# PowerSupplySimple.net
KiCad netlist of a schematic drawn in EAGLE
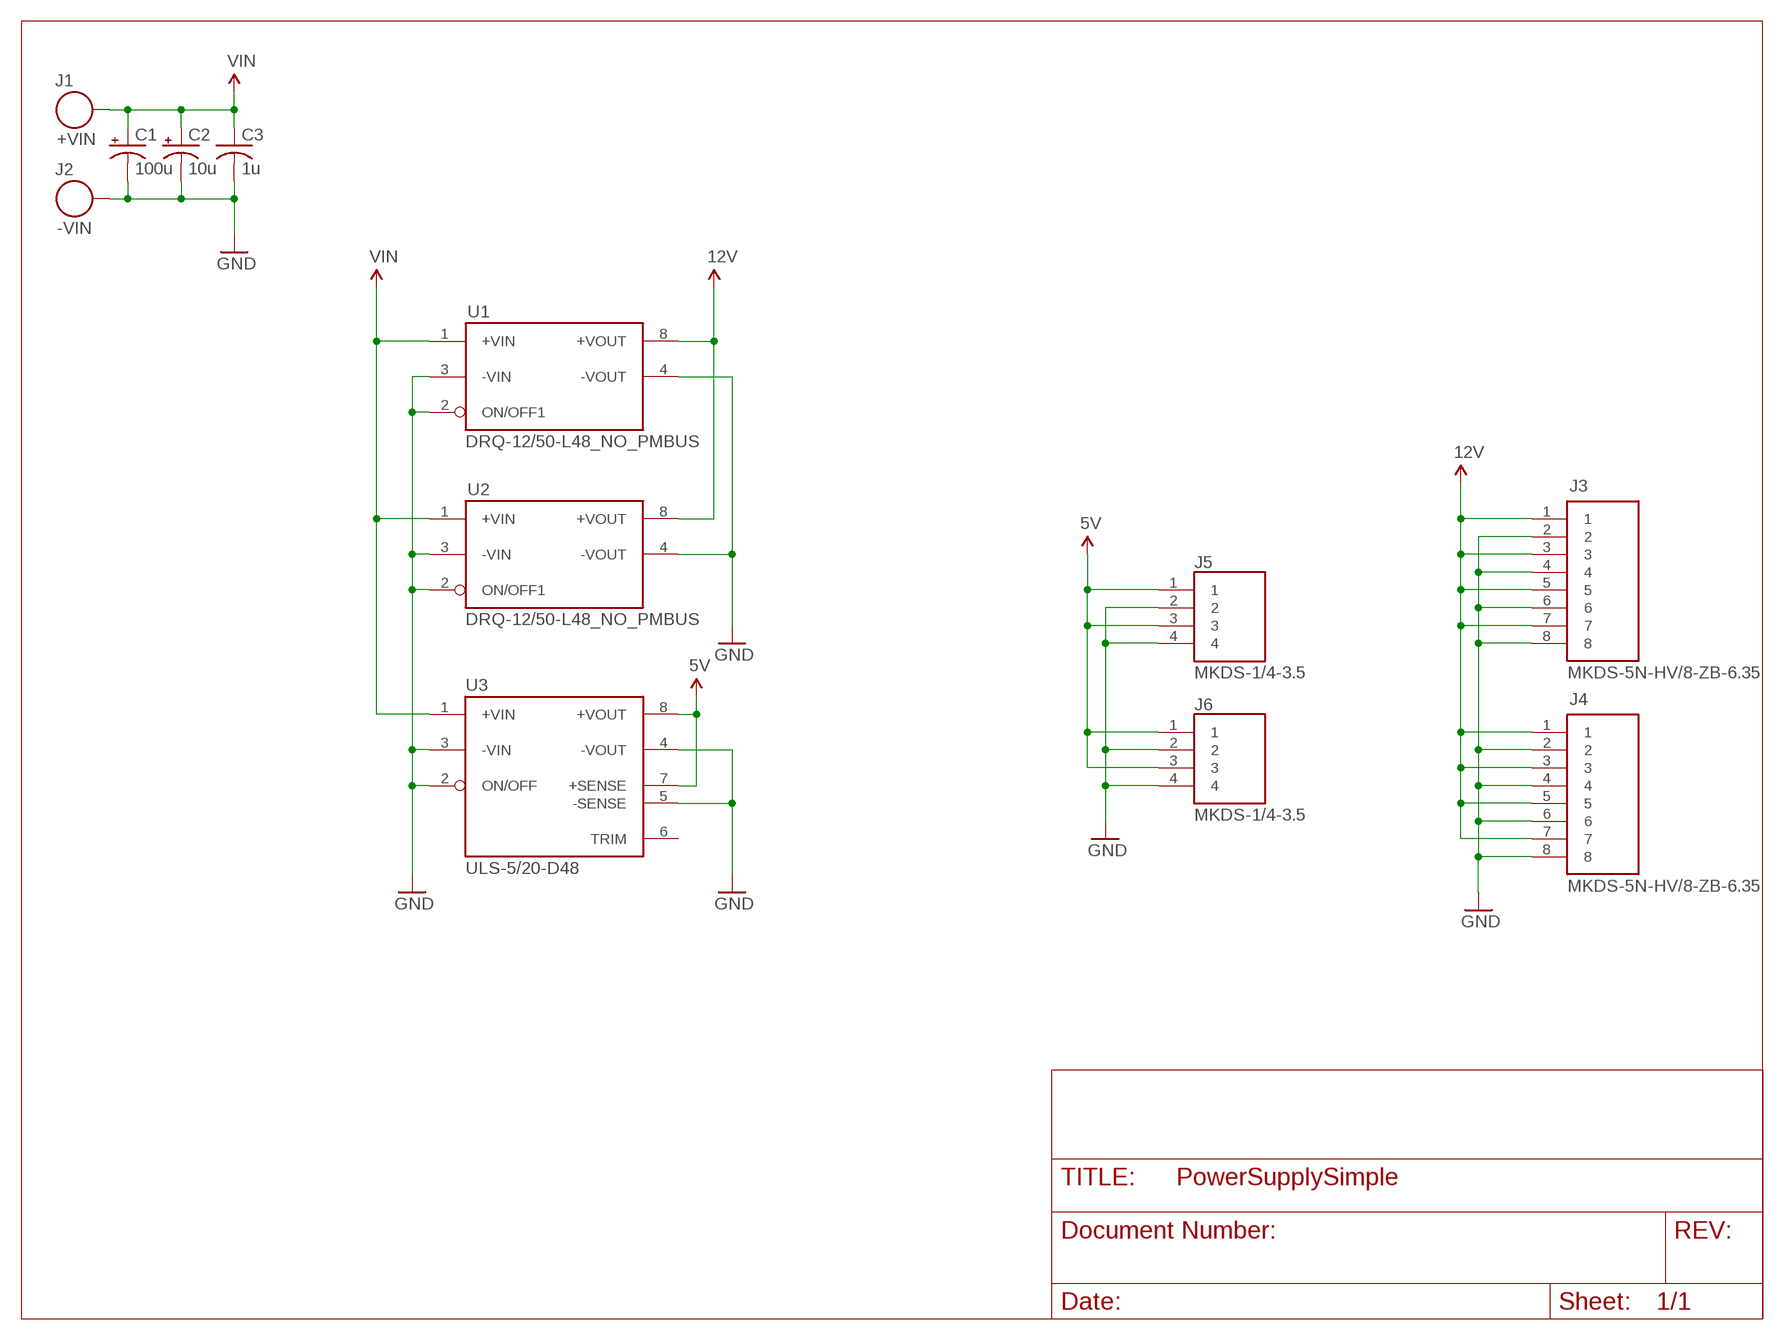
[diagram p0: schematic, sheet 1]

(export (version "E")
  (design (tool "Eeschema 10.0.6"))
  (components
    (comp (ref "C1")
      (value "100u")
      (footprint "eagle-import:PANASONIC_E")
      (libsource (lib "eagle-import") (part "CPOL-USE"))
    )
    (comp (ref "C2")
      (value "10u")
      (footprint "eagle-import:PANASONIC_E")
      (libsource (lib "eagle-import") (part "CPOL-USE"))
    )
    (comp (ref "C3")
      (value "1u")
      (footprint "eagle-import:C0603")
      (libsource (lib "eagle-import") (part "C-USC0603"))
    )
    (comp (ref "J1")
      (value "+VIN")
      (footprint "eagle-import:10AWG")
      (libsource (lib "eagle-import") (part "SINGLE_PIN"))
    )
    (comp (ref "J2")
      (value "-VIN")
      (footprint "eagle-import:10AWG")
      (libsource (lib "eagle-import") (part "SINGLE_PIN"))
    )
    (comp (ref "J3")
      (value "MKDS-5N-HV/8-ZB-6.35")
      (footprint "eagle-import:1777600")
      (libsource (lib "eagle-import") (part "MKDS-5N-HV/8-ZB-6.35"))
    )
    (comp (ref "J4")
      (value "MKDS-5N-HV/8-ZB-6.35")
      (footprint "eagle-import:1777600")
      (libsource (lib "eagle-import") (part "MKDS-5N-HV/8-ZB-6.35"))
    )
    (comp (ref "J5")
      (value "MKDS-1/4-3.5")
      (footprint "eagle-import:1751264")
      (libsource (lib "eagle-import") (part "MKDS-1/4-3.5"))
    )
    (comp (ref "J6")
      (value "MKDS-1/4-3.5")
      (footprint "eagle-import:1751264")
      (libsource (lib "eagle-import") (part "MKDS-1/4-3.5"))
    )
    (comp (ref "U1")
      (value "DRQ-12/50-L48_NO_PMBUS")
      (footprint "eagle-import:DRQ(NO_PMBUS)")
      (libsource (lib "eagle-import") (part "DRQ-12/50-L48_NO_PMBUS"))
    )
    (comp (ref "U2")
      (value "DRQ-12/50-L48_NO_PMBUS")
      (footprint "eagle-import:DRQ(NO_PMBUS)")
      (libsource (lib "eagle-import") (part "DRQ-12/50-L48_NO_PMBUS"))
    )
    (comp (ref "U3")
      (value "ULS-5/20-D48")
      (footprint "eagle-import:1_16_BRICK_THROUGH_HOLE")
      (libsource (lib "eagle-import") (part "ULS-5/20-D48"))
    )
  )
  (nets
    (net (code "1") (name "5V") (class "Default")
      (node (ref "J5") (pin "1") (pinfunction "1_1") (pintype "bidirectional"))
      (node (ref "J5") (pin "3") (pinfunction "3_3") (pintype "bidirectional"))
      (node (ref "J6") (pin "1") (pinfunction "1_1") (pintype "bidirectional"))
      (node (ref "J6") (pin "3") (pinfunction "3_3") (pintype "bidirectional"))
      (node (ref "U3") (pin "7") (pinfunction "+SENSE_7") (pintype "bidirectional"))
      (node (ref "U3") (pin "8") (pinfunction "+VOUT_8") (pintype "bidirectional"))
    )
    (net (code "2") (name "12V") (class "Default")
      (node (ref "J3") (pin "1") (pinfunction "1_1") (pintype "bidirectional"))
      (node (ref "J3") (pin "3") (pinfunction "3_3") (pintype "bidirectional"))
      (node (ref "J3") (pin "5") (pinfunction "5_5") (pintype "bidirectional"))
      (node (ref "J3") (pin "7") (pinfunction "7_7") (pintype "bidirectional"))
      (node (ref "J4") (pin "1") (pinfunction "1_1") (pintype "bidirectional"))
      (node (ref "J4") (pin "3") (pinfunction "3_3") (pintype "bidirectional"))
      (node (ref "J4") (pin "5") (pinfunction "5_5") (pintype "bidirectional"))
      (node (ref "J4") (pin "7") (pinfunction "7_7") (pintype "bidirectional"))
      (node (ref "U1") (pin "8") (pinfunction "+VOUT_8") (pintype "bidirectional"))
      (node (ref "U2") (pin "8") (pinfunction "+VOUT_8") (pintype "bidirectional"))
    )
    (net (code "3") (name "GND") (class "Default")
      (node (ref "C1") (pin "-") (pinfunction "-_-") (pintype "passive"))
      (node (ref "C2") (pin "-") (pinfunction "-_-") (pintype "passive"))
      (node (ref "C3") (pin "2") (pinfunction "2_2") (pintype "passive"))
      (node (ref "J2") (pin "P$1") (pinfunction "P$1_P$1") (pintype "bidirectional"))
      (node (ref "J3") (pin "2") (pinfunction "2_2") (pintype "bidirectional"))
      (node (ref "J3") (pin "4") (pinfunction "4_4") (pintype "bidirectional"))
      (node (ref "J3") (pin "6") (pinfunction "6_6") (pintype "bidirectional"))
      (node (ref "J3") (pin "8") (pinfunction "8_8") (pintype "bidirectional"))
      (node (ref "J4") (pin "2") (pinfunction "2_2") (pintype "bidirectional"))
      (node (ref "J4") (pin "4") (pinfunction "4_4") (pintype "bidirectional"))
      (node (ref "J4") (pin "6") (pinfunction "6_6") (pintype "bidirectional"))
      (node (ref "J4") (pin "8") (pinfunction "8_8") (pintype "bidirectional"))
      (node (ref "J5") (pin "2") (pinfunction "2_2") (pintype "bidirectional"))
      (node (ref "J5") (pin "4") (pinfunction "4_4") (pintype "bidirectional"))
      (node (ref "J6") (pin "2") (pinfunction "2_2") (pintype "bidirectional"))
      (node (ref "J6") (pin "4") (pinfunction "4_4") (pintype "bidirectional"))
      (node (ref "U1") (pin "2") (pinfunction "ON/OFF1_2") (pintype "bidirectional"))
      (node (ref "U1") (pin "3") (pinfunction "-VIN_3") (pintype "bidirectional"))
      (node (ref "U1") (pin "4") (pinfunction "-VOUT_4") (pintype "bidirectional"))
      (node (ref "U2") (pin "2") (pinfunction "ON/OFF1_2") (pintype "bidirectional"))
      (node (ref "U2") (pin "3") (pinfunction "-VIN_3") (pintype "bidirectional"))
      (node (ref "U2") (pin "4") (pinfunction "-VOUT_4") (pintype "bidirectional"))
      (node (ref "U3") (pin "2") (pinfunction "ON/OFF_2") (pintype "bidirectional"))
      (node (ref "U3") (pin "3") (pinfunction "-VIN_3") (pintype "bidirectional"))
      (node (ref "U3") (pin "4") (pinfunction "-VOUT_4") (pintype "bidirectional"))
      (node (ref "U3") (pin "5") (pinfunction "-SENSE_5") (pintype "bidirectional"))
    )
    (net (code "4") (name "VIN") (class "Default")
      (node (ref "C1") (pin "+") (pinfunction "+_+") (pintype "passive"))
      (node (ref "C2") (pin "+") (pinfunction "+_+") (pintype "passive"))
      (node (ref "C3") (pin "1") (pinfunction "1_1") (pintype "passive"))
      (node (ref "J1") (pin "P$1") (pinfunction "P$1_P$1") (pintype "bidirectional"))
      (node (ref "U1") (pin "1") (pinfunction "+VIN_1") (pintype "bidirectional"))
      (node (ref "U2") (pin "1") (pinfunction "+VIN_1") (pintype "bidirectional"))
      (node (ref "U3") (pin "1") (pinfunction "+VIN_1") (pintype "bidirectional"))
    )
    (net (code "5") (name "unconnected-(U3-TRIM-Pad6)") (class "Default")
      (node (ref "U3") (pin "6") (pinfunction "TRIM_6") (pintype "bidirectional"))
    )
  )
)
